# 02_ESP32.net
KiCad netlist of a schematic drawn in Altium Designer
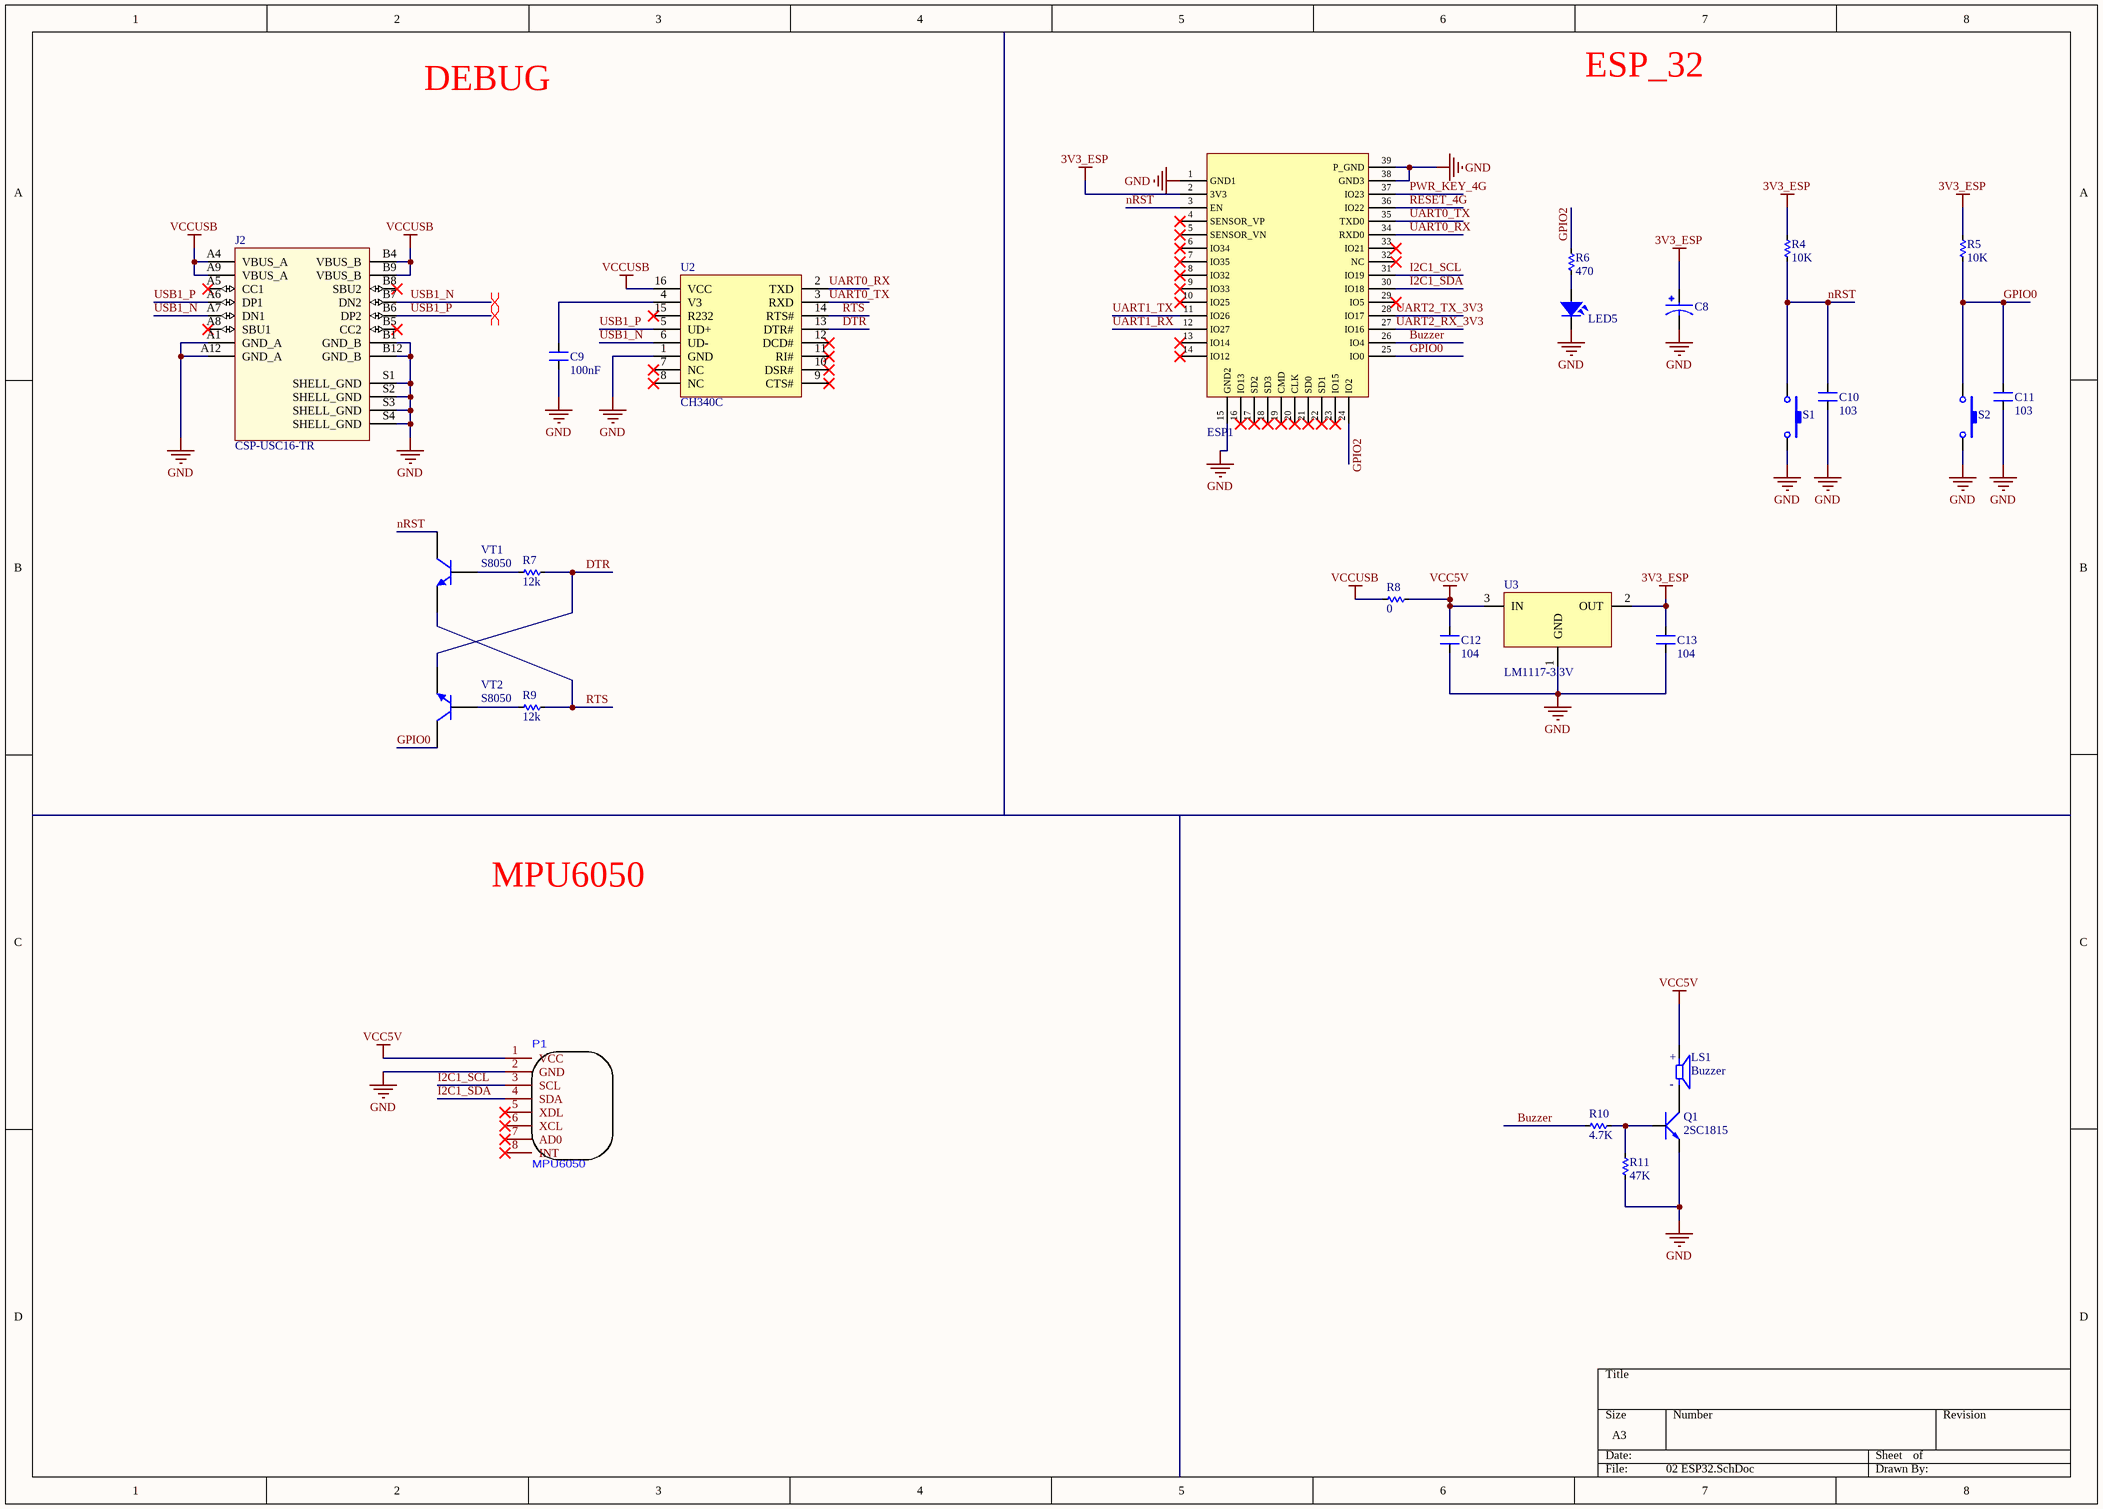
[diagram p0: 02 ESP32.SchDoc]

(export (version "E")
  (design (tool "Eeschema 10.0.6"))
  (components
    (comp (ref "C8")
      (value "CAP_TANTALUM_SMD")
      (footprint "CAP_TANTALUM_3216")
      (description "Capacitor, Tantalum")
      (fields (field (name "MF") "AVX") (field (name "MP") "TAJB475K025RNJ"))
      (libsource (lib "My Library") (part "CAP_TANTALUM_SMD"))
    )
    (comp (ref "C9")
      (value "100nF")
      (footprint "HuanHaui_FEETEAM:C 0603")
      (libsource (lib "HuanHaui_FEETEAM") (part "CAP_SMD"))
    )
    (comp (ref "C10")
      (value "103")
      (footprint "C-0603")
      (description "Cap SMD")
      (libsource (lib "My Library") (part "CM"))
    )
    (comp (ref "C11")
      (value "103")
      (footprint "C-0603")
      (description "Cap SMD")
      (libsource (lib "My Library") (part "CM"))
    )
    (comp (ref "C12")
      (value "104")
      (footprint "HuanHaui_FEETEAM:C 0603")
      (libsource (lib "HuanHaui_FEETEAM") (part "CAP_SMD"))
    )
    (comp (ref "C13")
      (value "104")
      (footprint "HuanHaui_FEETEAM:C 0603")
      (libsource (lib "HuanHaui_FEETEAM") (part "CAP_SMD"))
    )
    (comp (ref "ESP1")
      (value "ESP32")
      (footprint "My Library:ESP_WROOM_32")
      (libsource (lib "My Library") (part "ESP-WROOM-32"))
    )
    (comp (ref "J2")
      (value "CSP-USC16-TR")
      (footprint "HuanHaui_FEETEAM:VALCON_CSP-USC16-TR")
      (description "CSP-USC16-TR Valcon USB Type C Surface Mount PCB Socket")
      (fields (field (name "MF") "Valcon"))
      (libsource (lib "HuanHaui_FEETEAM") (part "CSP-USC16-TR"))
    )
    (comp (ref "LED5")
      (value "LED")
      (footprint "My Library:LED-0603")
      (libsource (lib "My Library") (part "LED SMD"))
    )
    (comp (ref "LS1")
      (value "Buzzer")
      (footprint "Buzzer-9MM")
      (fields (field (name "MP") "CST-951AP"))
      (libsource (lib "My Library") (part "Buzzer"))
    )
    (comp (ref "P1")
      (value "MPU6050")
      (footprint "MPU6050")
      (libsource (lib "MinhNguyenCao") (part "MPU6050"))
    )
    (comp (ref "Q1")
      (value "2SC1815")
      (footprint "SOT23-321")
      (description "NPN 600mW, ECB")
      (libsource (lib "My Library") (part "2SC1815"))
    )
    (comp (ref "R4")
      (value "10K")
      (footprint "RES-SMD-0603")
      (description "Resistor")
      (fields
        (field (name "MANUFACTURER") "Generic Components")
        (field (name "PUBLISHER") "Altium Hobart Technology Centre")
      )
      (libsource (lib "My Library") (part "Res-SMD"))
    )
    (comp (ref "R5")
      (value "10K")
      (footprint "RES-SMD-0603")
      (description "Resistor")
      (fields
        (field (name "MANUFACTURER") "Generic Components")
        (field (name "PUBLISHER") "Altium Hobart Technology Centre")
      )
      (libsource (lib "My Library") (part "Res-SMD"))
    )
    (comp (ref "R6")
      (value "470")
      (footprint "HuanHaui_FEETEAM:RES-SMD-0402")
      (description "RES_SMD")
      (fields
        (field (name "MANUFACTURER") "Generic Components")
        (field (name "PUBLISHER") "Altium Hobart Technology Centre")
      )
      (libsource (lib "HuanHaui_FEETEAM") (part "Res-SMD"))
    )
    (comp (ref "R7")
      (value "12k")
      (footprint "HuanHaui_FEETEAM:RES-SMD-0402")
      (description "RES_SMD")
      (fields
        (field (name "MANUFACTURER") "Generic Components")
        (field (name "PUBLISHER") "Altium Hobart Technology Centre")
      )
      (libsource (lib "HuanHaui_FEETEAM") (part "Res-SMD"))
    )
    (comp (ref "R8")
      (value "0")
      (footprint "RES-SMD-0603")
      (description "Resistor")
      (fields
        (field (name "MANUFACTURER") "Generic Components")
        (field (name "PUBLISHER") "Altium Hobart Technology Centre")
      )
      (libsource (lib "My Library") (part "Res-SMD"))
    )
    (comp (ref "R9")
      (value "12k")
      (footprint "HuanHaui_FEETEAM:RES-SMD-0402")
      (description "RES_SMD")
      (fields
        (field (name "MANUFACTURER") "Generic Components")
        (field (name "PUBLISHER") "Altium Hobart Technology Centre")
      )
      (libsource (lib "HuanHaui_FEETEAM") (part "Res-SMD"))
    )
    (comp (ref "R10")
      (value "4.7K")
      (footprint "RES-SMD-0603")
      (description "Resistor")
      (fields
        (field (name "MANUFACTURER") "Generic Components")
        (field (name "PUBLISHER") "Altium Hobart Technology Centre")
      )
      (libsource (lib "My Library") (part "Res-SMD"))
    )
    (comp (ref "R11")
      (value "47K")
      (footprint "RES-SMD-0603")
      (description "Resistor")
      (fields
        (field (name "MANUFACTURER") "Generic Components")
        (field (name "PUBLISHER") "Altium Hobart Technology Centre")
      )
      (libsource (lib "My Library") (part "Res-SMD"))
    )
    (comp (ref "S1")
      (value "SW-SMD")
      (footprint "SW_B3U-1000P")
      (description "Switch")
      (fields (field (name "PUBLISHER") "Altium Limited"))
      (libsource (lib "My Library") (part "SW-SMD"))
    )
    (comp (ref "S2")
      (value "SW-SMD")
      (footprint "SW_B3U-1000P")
      (description "Switch")
      (fields (field (name "PUBLISHER") "Altium Limited"))
      (libsource (lib "My Library") (part "SW-SMD"))
    )
    (comp (ref "U2")
      (value "CH340C")
      (footprint "SOIC16_50_284_25X90_SMT")
      (description "USB Bridge, USB to UART USB 2.0 UART Interface")
      (fields (field (name "MANUFACTURER") "Olimex"))
      (libsource (lib "IC") (part "CH340C"))
    )
    (comp (ref "U3")
      (value "LM1117-3.3V")
      (footprint "SOT223")
      (description "800mA Low-Dropout Linear Regulator")
      (fields (field (name "CREATOR") "Nguyen Ba Bien"))
      (libsource (lib "HuanHaui_FEETEAM") (part "LM1117"))
    )
    (comp (ref "VT1")
      (value "S8050")
      (footprint "SMT_TRIODE_NPN")
      (description "Surface mount NPN transistor, package SOT-23")
      (libsource (lib "esp8266") (part "SMT_TRIODE_NPN"))
    )
    (comp (ref "VT2")
      (value "S8050")
      (footprint "SMT_TRIODE_NPN")
      (description "Surface mount NPN transistor, package SOT-23")
      (libsource (lib "esp8266") (part "SMT_TRIODE_NPN"))
    )
  )
  (nets
    (net (code "1") (name "/Buzzer") (class "Default")
      (node (ref "ESP1") (pin "26") (pinfunction "IO4_26") (pintype "passive"))
      (node (ref "R10") (pin "1") (pinfunction "1_1") (pintype "passive"))
    )
    (net (code "2") (name "/DTR") (class "Default")
      (node (ref "R7") (pin "1") (pinfunction "1_1") (pintype "passive"))
      (node (ref "U2") (pin "13") (pinfunction "DTR#_13") (pintype "passive"))
      (node (ref "VT2") (pin "2") (pinfunction "E_2") (pintype "passive"))
    )
    (net (code "3") (name "/GPIO0") (class "Default")
      (node (ref "C11") (pin "2") (pinfunction "2_2") (pintype "passive"))
      (node (ref "ESP1") (pin "25") (pinfunction "IO0_25") (pintype "passive"))
      (node (ref "R5") (pin "2") (pinfunction "2_2") (pintype "passive"))
      (node (ref "S2") (pin "1") (pinfunction "1_1") (pintype "passive"))
      (node (ref "VT2") (pin "3") (pinfunction "C_3") (pintype "passive"))
    )
    (net (code "4") (name "/GPIO2") (class "Default")
      (node (ref "ESP1") (pin "24") (pinfunction "IO2_24") (pintype "passive"))
      (node (ref "R6") (pin "2") (pinfunction "2_2") (pintype "passive"))
    )
    (net (code "5") (name "/I2C1_SCL") (class "Default")
      (node (ref "ESP1") (pin "31") (pinfunction "IO19_31") (pintype "passive"))
      (node (ref "P1") (pin "3") (pinfunction "SCL_3") (pintype "passive"))
    )
    (net (code "6") (name "/I2C1_SDA") (class "Default")
      (node (ref "ESP1") (pin "30") (pinfunction "IO18_30") (pintype "passive"))
      (node (ref "P1") (pin "4") (pinfunction "SDA_4") (pintype "passive"))
    )
    (net (code "7") (name "/PWR_KEY_4G") (class "Default")
      (node (ref "ESP1") (pin "37") (pinfunction "IO23_37") (pintype "passive"))
    )
    (net (code "8") (name "/RESET_4G") (class "Default")
      (node (ref "ESP1") (pin "36") (pinfunction "IO22_36") (pintype "passive"))
    )
    (net (code "9") (name "/RTS") (class "Default")
      (node (ref "R9") (pin "1") (pinfunction "1_1") (pintype "passive"))
      (node (ref "U2") (pin "14") (pinfunction "RTS#_14") (pintype "passive"))
      (node (ref "VT1") (pin "2") (pinfunction "E_2") (pintype "passive"))
    )
    (net (code "10") (name "/UART0_RX") (class "Default")
      (node (ref "ESP1") (pin "34") (pinfunction "RXD0_34") (pintype "passive"))
      (node (ref "U2") (pin "2") (pinfunction "TXD_2") (pintype "passive"))
    )
    (net (code "11") (name "/UART0_TX") (class "Default")
      (node (ref "ESP1") (pin "35") (pinfunction "TXD0_35") (pintype "passive"))
      (node (ref "U2") (pin "3") (pinfunction "RXD_3") (pintype "passive"))
    )
    (net (code "12") (name "/UART1_RX") (class "Default")
      (node (ref "ESP1") (pin "12") (pinfunction "IO27_12") (pintype "passive"))
    )
    (net (code "13") (name "/UART1_TX") (class "Default")
      (node (ref "ESP1") (pin "11") (pinfunction "IO26_11") (pintype "passive"))
    )
    (net (code "14") (name "/UART2_RX_3V3") (class "Default")
      (node (ref "ESP1") (pin "27") (pinfunction "IO16_27") (pintype "passive"))
    )
    (net (code "15") (name "/UART2_TX_3V3") (class "Default")
      (node (ref "ESP1") (pin "28") (pinfunction "IO17_28") (pintype "passive"))
    )
    (net (code "16") (name "/USB1_N") (class "Default")
      (node (ref "J2") (pin "A7") (pinfunction "DN1_A7") (pintype "bidirectional"))
      (node (ref "J2") (pin "B7") (pinfunction "DN2_B7") (pintype "bidirectional"))
      (node (ref "U2") (pin "6") (pinfunction "UD-_6") (pintype "passive"))
    )
    (net (code "17") (name "/USB1_P") (class "Default")
      (node (ref "J2") (pin "A6") (pinfunction "DP1_A6") (pintype "bidirectional"))
      (node (ref "J2") (pin "B6") (pinfunction "DP2_B6") (pintype "bidirectional"))
      (node (ref "U2") (pin "5") (pinfunction "UD+_5") (pintype "passive"))
    )
    (net (code "18") (name "/nRST") (class "Default")
      (node (ref "C10") (pin "2") (pinfunction "2_2") (pintype "passive"))
      (node (ref "ESP1") (pin "3") (pinfunction "EN_3") (pintype "passive"))
      (node (ref "R4") (pin "2") (pinfunction "2_2") (pintype "passive"))
      (node (ref "S1") (pin "1") (pinfunction "1_1") (pintype "passive"))
      (node (ref "VT1") (pin "3") (pinfunction "C_3") (pintype "passive"))
    )
    (net (code "19") (name "3V3_ESP") (class "Default")
      (node (ref "C13") (pin "1") (pinfunction "1_1") (pintype "passive"))
      (node (ref "C8") (pin "1") (pinfunction "1_1") (pintype "passive"))
      (node (ref "ESP1") (pin "2") (pinfunction "3V3_2") (pintype "passive"))
      (node (ref "R4") (pin "1") (pinfunction "1_1") (pintype "passive"))
      (node (ref "R5") (pin "1") (pinfunction "1_1") (pintype "passive"))
      (node (ref "U3") (pin "2") (pinfunction "OUT_2") (pintype "passive"))
    )
    (net (code "20") (name "GND") (class "Default")
      (node (ref "C10") (pin "1") (pinfunction "1_1") (pintype "passive"))
      (node (ref "C11") (pin "1") (pinfunction "1_1") (pintype "passive"))
      (node (ref "C12") (pin "2") (pinfunction "2_2") (pintype "passive"))
      (node (ref "C13") (pin "2") (pinfunction "2_2") (pintype "passive"))
      (node (ref "C8") (pin "2") (pinfunction "2_2") (pintype "passive"))
      (node (ref "C9") (pin "1") (pinfunction "1_1") (pintype "passive"))
      (node (ref "ESP1") (pin "1") (pinfunction "GND1_1") (pintype "passive"))
      (node (ref "ESP1") (pin "15") (pinfunction "GND2_15") (pintype "passive"))
      (node (ref "ESP1") (pin "38") (pinfunction "GND3_38") (pintype "passive"))
      (node (ref "ESP1") (pin "39") (pinfunction "P_GND_39") (pintype "passive"))
      (node (ref "J2") (pin "A1") (pinfunction "GND_A_A1") (pintype "power_in"))
      (node (ref "J2") (pin "A12") (pinfunction "GND_A_A12") (pintype "power_in"))
      (node (ref "J2") (pin "B1") (pinfunction "GND_B_B1") (pintype "power_in"))
      (node (ref "J2") (pin "B12") (pinfunction "GND_B_B12") (pintype "power_in"))
      (node (ref "J2") (pin "S1") (pinfunction "SHELL_GND_S1") (pintype "power_in"))
      (node (ref "J2") (pin "S2") (pinfunction "SHELL_GND_S2") (pintype "power_in"))
      (node (ref "J2") (pin "S3") (pinfunction "SHELL_GND_S3") (pintype "power_in"))
      (node (ref "J2") (pin "S4") (pinfunction "SHELL_GND_S4") (pintype "power_in"))
      (node (ref "LED5") (pin "2") (pinfunction "2_2") (pintype "passive"))
      (node (ref "P1") (pin "2") (pinfunction "GND_2") (pintype "passive"))
      (node (ref "Q1") (pin "1") (pinfunction "E_1") (pintype "passive"))
      (node (ref "R11") (pin "1") (pinfunction "1_1") (pintype "passive"))
      (node (ref "S1") (pin "2") (pinfunction "2_2") (pintype "passive"))
      (node (ref "S2") (pin "2") (pinfunction "2_2") (pintype "passive"))
      (node (ref "U2") (pin "1") (pinfunction "GND_1") (pintype "passive"))
      (node (ref "U3") (pin "1") (pinfunction "GND_1") (pintype "passive"))
    )
    (net (code "21") (name "Net-(LED5-Pad1)") (class "Default")
      (node (ref "LED5") (pin "1") (pinfunction "1_1") (pintype "passive"))
      (node (ref "R6") (pin "1") (pinfunction "1_1") (pintype "passive"))
    )
    (net (code "22") (name "Net-(LS1-M)") (class "Default")
      (node (ref "LS1") (pin "2") (pinfunction "M_2") (pintype "passive"))
      (node (ref "Q1") (pin "2") (pinfunction "C_2") (pintype "passive"))
    )
    (net (code "23") (name "Net-(Q1-B)") (class "Default")
      (node (ref "Q1") (pin "3") (pinfunction "B_3") (pintype "passive"))
      (node (ref "R10") (pin "2") (pinfunction "2_2") (pintype "passive"))
      (node (ref "R11") (pin "2") (pinfunction "2_2") (pintype "passive"))
    )
    (net (code "24") (name "Net-(U2-V3)") (class "Default")
      (node (ref "C9") (pin "2") (pinfunction "2_2") (pintype "passive"))
      (node (ref "U2") (pin "4") (pinfunction "V3_4") (pintype "passive"))
    )
    (net (code "25") (name "Net-(VT1-B)") (class "Default")
      (node (ref "R7") (pin "2") (pinfunction "2_2") (pintype "passive"))
      (node (ref "VT1") (pin "1") (pinfunction "B_1") (pintype "passive"))
    )
    (net (code "26") (name "Net-(VT2-B)") (class "Default")
      (node (ref "R9") (pin "2") (pinfunction "2_2") (pintype "passive"))
      (node (ref "VT2") (pin "1") (pinfunction "B_1") (pintype "passive"))
    )
    (net (code "27") (name "VCC5V") (class "Default")
      (node (ref "C12") (pin "1") (pinfunction "1_1") (pintype "passive"))
      (node (ref "LS1") (pin "1") (pinfunction "P_1") (pintype "passive"))
      (node (ref "P1") (pin "1") (pinfunction "VCC_1") (pintype "passive"))
      (node (ref "R8") (pin "1") (pinfunction "1_1") (pintype "passive"))
      (node (ref "U3") (pin "3") (pinfunction "IN_3") (pintype "passive"))
    )
    (net (code "28") (name "VCCUSB") (class "Default")
      (node (ref "J2") (pin "A4") (pinfunction "VBUS_A_A4") (pintype "power_in"))
      (node (ref "J2") (pin "A9") (pinfunction "VBUS_A_A9") (pintype "power_in"))
      (node (ref "J2") (pin "B4") (pinfunction "VBUS_B_B4") (pintype "power_in"))
      (node (ref "J2") (pin "B9") (pinfunction "VBUS_B_B9") (pintype "power_in"))
      (node (ref "R8") (pin "2") (pinfunction "2_2") (pintype "passive"))
      (node (ref "U2") (pin "16") (pinfunction "VCC_16") (pintype "passive"))
    )
    (net (code "29") (name "unconnected-(ESP1-CLK-Pad20)") (class "Default")
      (node (ref "ESP1") (pin "20") (pinfunction "CLK_20") (pintype "passive+no_connect"))
    )
    (net (code "30") (name "unconnected-(ESP1-CMD-Pad19)") (class "Default")
      (node (ref "ESP1") (pin "19") (pinfunction "CMD_19") (pintype "passive+no_connect"))
    )
    (net (code "31") (name "unconnected-(ESP1-IO5-Pad29)") (class "Default")
      (node (ref "ESP1") (pin "29") (pinfunction "IO5_29") (pintype "passive+no_connect"))
    )
    (net (code "32") (name "unconnected-(ESP1-IO12-Pad14)") (class "Default")
      (node (ref "ESP1") (pin "14") (pinfunction "IO12_14") (pintype "passive+no_connect"))
    )
    (net (code "33") (name "unconnected-(ESP1-IO13-Pad16)") (class "Default")
      (node (ref "ESP1") (pin "16") (pinfunction "IO13_16") (pintype "passive+no_connect"))
    )
    (net (code "34") (name "unconnected-(ESP1-IO14-Pad13)") (class "Default")
      (node (ref "ESP1") (pin "13") (pinfunction "IO14_13") (pintype "passive+no_connect"))
    )
    (net (code "35") (name "unconnected-(ESP1-IO15-Pad23)") (class "Default")
      (node (ref "ESP1") (pin "23") (pinfunction "IO15_23") (pintype "passive+no_connect"))
    )
    (net (code "36") (name "unconnected-(ESP1-IO21-Pad33)") (class "Default")
      (node (ref "ESP1") (pin "33") (pinfunction "IO21_33") (pintype "passive+no_connect"))
    )
    (net (code "37") (name "unconnected-(ESP1-IO25-Pad10)") (class "Default")
      (node (ref "ESP1") (pin "10") (pinfunction "IO25_10") (pintype "passive+no_connect"))
    )
    (net (code "38") (name "unconnected-(ESP1-IO32-Pad8)") (class "Default")
      (node (ref "ESP1") (pin "8") (pinfunction "IO32_8") (pintype "passive+no_connect"))
    )
    (net (code "39") (name "unconnected-(ESP1-IO33-Pad9)") (class "Default")
      (node (ref "ESP1") (pin "9") (pinfunction "IO33_9") (pintype "passive+no_connect"))
    )
    (net (code "40") (name "unconnected-(ESP1-IO34-Pad6)") (class "Default")
      (node (ref "ESP1") (pin "6") (pinfunction "IO34_6") (pintype "passive+no_connect"))
    )
    (net (code "41") (name "unconnected-(ESP1-IO35-Pad7)") (class "Default")
      (node (ref "ESP1") (pin "7") (pinfunction "IO35_7") (pintype "passive+no_connect"))
    )
    (net (code "42") (name "unconnected-(ESP1-NC-Pad32)") (class "Default")
      (node (ref "ESP1") (pin "32") (pinfunction "NC_32") (pintype "passive+no_connect"))
    )
    (net (code "43") (name "unconnected-(ESP1-SD0-Pad21)") (class "Default")
      (node (ref "ESP1") (pin "21") (pinfunction "SD0_21") (pintype "passive+no_connect"))
    )
    (net (code "44") (name "unconnected-(ESP1-SD1-Pad22)") (class "Default")
      (node (ref "ESP1") (pin "22") (pinfunction "SD1_22") (pintype "passive+no_connect"))
    )
    (net (code "45") (name "unconnected-(ESP1-SD2-Pad17)") (class "Default")
      (node (ref "ESP1") (pin "17") (pinfunction "SD2_17") (pintype "passive+no_connect"))
    )
    (net (code "46") (name "unconnected-(ESP1-SD3-Pad18)") (class "Default")
      (node (ref "ESP1") (pin "18") (pinfunction "SD3_18") (pintype "passive+no_connect"))
    )
    (net (code "47") (name "unconnected-(ESP1-SENSOR_VN-Pad5)") (class "Default")
      (node (ref "ESP1") (pin "5") (pinfunction "SENSOR_VN_5") (pintype "passive+no_connect"))
    )
    (net (code "48") (name "unconnected-(ESP1-SENSOR_VP-Pad4)") (class "Default")
      (node (ref "ESP1") (pin "4") (pinfunction "SENSOR_VP_4") (pintype "passive+no_connect"))
    )
    (net (code "49") (name "unconnected-(J2-CC1-PadA5)") (class "Default")
      (node (ref "J2") (pin "A5") (pinfunction "CC1_A5") (pintype "bidirectional+no_connect"))
    )
    (net (code "50") (name "unconnected-(J2-CC2-PadB5)") (class "Default")
      (node (ref "J2") (pin "B5") (pinfunction "CC2_B5") (pintype "bidirectional+no_connect"))
    )
    (net (code "51") (name "unconnected-(J2-SBU1-PadA8)") (class "Default")
      (node (ref "J2") (pin "A8") (pinfunction "SBU1_A8") (pintype "bidirectional+no_connect"))
    )
    (net (code "52") (name "unconnected-(J2-SBU2-PadB8)") (class "Default")
      (node (ref "J2") (pin "B8") (pinfunction "SBU2_B8") (pintype "bidirectional+no_connect"))
    )
    (net (code "53") (name "unconnected-(P1-AD0-Pad7)") (class "Default")
      (node (ref "P1") (pin "7") (pinfunction "AD0_7") (pintype "passive+no_connect"))
    )
    (net (code "54") (name "unconnected-(P1-INT-Pad8)") (class "Default")
      (node (ref "P1") (pin "8") (pinfunction "INT_8") (pintype "passive+no_connect"))
    )
    (net (code "55") (name "unconnected-(P1-XCL-Pad6)") (class "Default")
      (node (ref "P1") (pin "6") (pinfunction "XCL_6") (pintype "passive+no_connect"))
    )
    (net (code "56") (name "unconnected-(P1-XDL-Pad5)") (class "Default")
      (node (ref "P1") (pin "5") (pinfunction "XDL_5") (pintype "passive+no_connect"))
    )
    (net (code "57") (name "unconnected-(U2-CTS#-Pad9)") (class "Default")
      (node (ref "U2") (pin "9") (pinfunction "CTS#_9") (pintype "passive+no_connect"))
    )
    (net (code "58") (name "unconnected-(U2-DCD#-Pad12)") (class "Default")
      (node (ref "U2") (pin "12") (pinfunction "DCD#_12") (pintype "passive+no_connect"))
    )
    (net (code "59") (name "unconnected-(U2-DSR#-Pad10)") (class "Default")
      (node (ref "U2") (pin "10") (pinfunction "DSR#_10") (pintype "passive+no_connect"))
    )
    (net (code "60") (name "unconnected-(U2-NC-Pad7)") (class "Default")
      (node (ref "U2") (pin "7") (pinfunction "NC_7") (pintype "passive+no_connect"))
    )
    (net (code "61") (name "unconnected-(U2-NC-Pad8)") (class "Default")
      (node (ref "U2") (pin "8") (pinfunction "NC_8") (pintype "passive+no_connect"))
    )
    (net (code "62") (name "unconnected-(U2-R232-Pad15)") (class "Default")
      (node (ref "U2") (pin "15") (pinfunction "R232_15") (pintype "passive+no_connect"))
    )
    (net (code "63") (name "unconnected-(U2-RI#-Pad11)") (class "Default")
      (node (ref "U2") (pin "11") (pinfunction "RI#_11") (pintype "passive+no_connect"))
    )
  )
)
